# SoC.net
KiCad netlist of a schematic drawn in Altium Designer
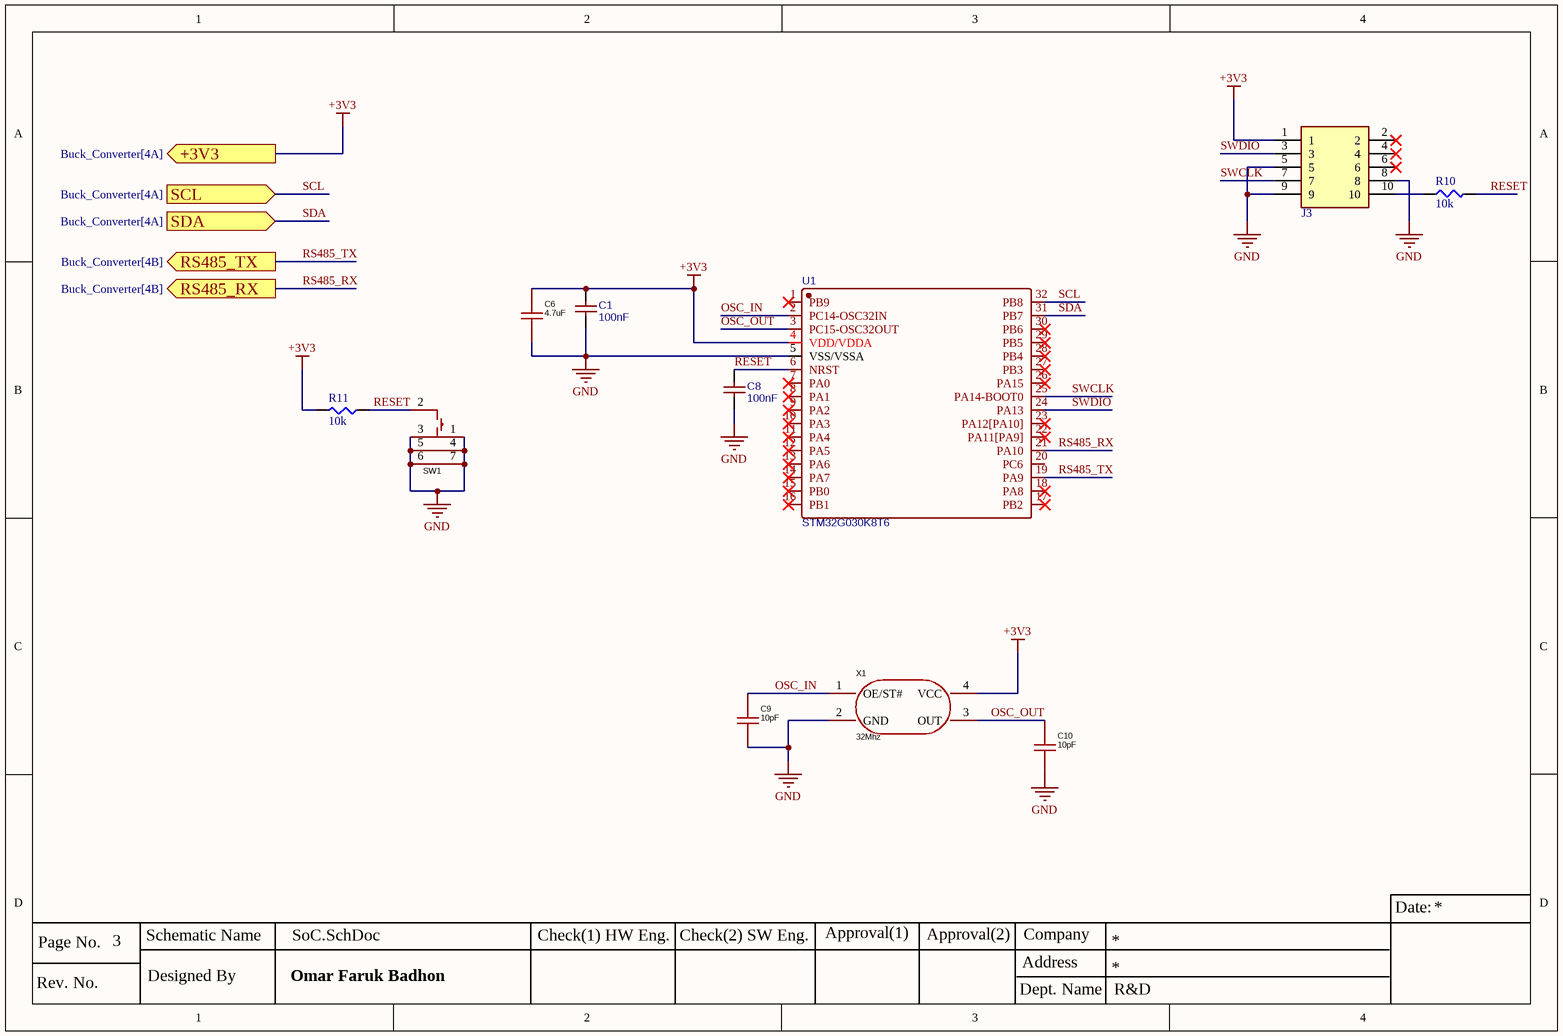
[diagram p0: SoC.SchDoc]

(export (version "E")
  (design (tool "Eeschema 10.0.6"))
  (components
    (comp (ref "C1")
      (value "100nF")
      (footprint "Cap 100nF 16V")
      (description "16V 100nF X7R ±10% 0603 Multilayer Ceramic Capacitors MLCC - SMD/SMT ROHS")
      (fields
        (field (name "MANUFACTURER") "muRata(村田)")
        (field (name "MANUFACTURER PART") "GRM188R71C104KA01D")
      )
      (libsource (lib "Sch lib") (part "Cap 100nF"))
    )
    (comp (ref "C6")
      (value "4.7uF")
      (footprint "Cap 4.7uF")
      (description "16V 4.7uF X7S ±10% 0603 Multilayer Ceramic Capacitors MLCC - SMD/SMT ROHS")
      (fields
        (field (name "MANUFACTURER") "muRata(村田)")
        (field (name "MANUFACTURER PART") "GRM188C71C475KE21D")
      )
      (libsource (lib "Sch lib") (part "GRM188C71C475KE21D"))
    )
    (comp (ref "C8")
      (value "100nF")
      (footprint "Cap 100nF 16V")
      (description "16V 100nF X7R ±10% 0603 Multilayer Ceramic Capacitors MLCC - SMD/SMT ROHS")
      (fields
        (field (name "MANUFACTURER") "muRata(村田)")
        (field (name "MANUFACTURER PART") "GRM188R71C104KA01D")
      )
      (libsource (lib "Sch lib") (part "Cap 100nF"))
    )
    (comp (ref "C9")
      (value "10pF")
      (footprint "Cap 10pF")
      (description "25V 10pF NP0 ±5% 0603  Multilayer Ceramic Capacitors MLCC - SMD/SMT ROHS")
      (fields
        (field (name "MANUFACTURER") "YAGEO(国巨)")
        (field (name "MANUFACTURER PART") "CC0603JRNPO8BN100")
      )
      (libsource (lib "Sch lib") (part "Cap 10pF"))
    )
    (comp (ref "C10")
      (value "10pF")
      (footprint "Cap 10pF")
      (description "25V 10pF NP0 ±5% 0603  Multilayer Ceramic Capacitors MLCC - SMD/SMT ROHS")
      (fields
        (field (name "MANUFACTURER") "YAGEO(国巨)")
        (field (name "MANUFACTURER PART") "CC0603JRNPO8BN100")
      )
      (libsource (lib "Sch lib") (part "Cap 10pF"))
    )
    (comp (ref "J3")
      (value "20021121-00010C4LF")
      (footprint "JTAG")
      (description "Headers & Wire Housings 1.27x1.27mm BTB, Hdr Unshrd, SMT, 10 Pos")
      (fields (field (name "MOUSER PART NUMBER") "649-202112100010C4LF"))
      (libsource (lib "Sch lib") (part "JTAG"))
    )
    (comp (ref "R10")
      (value "10k")
      (footprint "Res 10K")
      (description "RES SMD 10K OHM 1% 1/4W 0603")
      (fields
        (field (name "PART NUMBER") "ERJ-PA3F1002V")
        (field (name "DIGI-KEY PART NUMBER") "P10KBYCT-ND")
      )
      (libsource (lib "Sch lib") (part "ERJ-PA3F1002V_1"))
    )
    (comp (ref "R11")
      (value "10k")
      (footprint "Res 10K")
      (description "RES SMD 10K OHM 1% 1/4W 0603")
      (fields
        (field (name "PART NUMBER") "ERJ-PA3F1002V")
        (field (name "DIGI-KEY PART NUMBER") "P10KBYCT-ND")
      )
      (libsource (lib "Sch lib") (part "ERJ-PA3F1002V_1"))
    )
    (comp (ref "SW1")
      (value "TSA020B3418A02")
      (footprint "Push Button")
      (fields (field (name "MANUFACTURER") "BZCN(博众电气)"))
      (libsource (lib "Sch lib") (part "Push Button"))
    )
    (comp (ref "U1")
      (value "STM32G030K8T6")
      (footprint "STM32G030K8T6")
      (fields (field (name "MANUFACTURER") "ST(意法半导体)") (field (name "CONTRIBUTOR") "LCSC"))
      (libsource (lib "Sch lib") (part "STM32G030K8T6"))
    )
    (comp (ref "X1")
      (value "32Mhz")
      (footprint "Crystal 32MHz")
      (fields (field (name "MANUFACTURER") "EPSON(爱普生)") (field (name "MANUFACTURER PART") "X1G0044810009"))
      (libsource (lib "Sch lib") (part "Crystal"))
    )
  )
  (nets
    (net (code "1") (name "+3V3") (class "Default")
      (node (ref "C1") (pin "2") (pinfunction "2_2") (pintype "passive"))
      (node (ref "C6") (pin "1") (pinfunction "1_1") (pintype "passive"))
      (node (ref "J3") (pin "1") (pinfunction "1_1") (pintype "passive"))
      (node (ref "R11") (pin "2") (pinfunction "2_2") (pintype "passive"))
      (node (ref "U1") (pin "4") (pinfunction "VDD/VDDA_4") (pintype "passive"))
      (node (ref "X1") (pin "4") (pinfunction "VCC_4") (pintype "passive"))
    )
    (net (code "2") (name "/OSC_IN") (class "Default")
      (node (ref "C9") (pin "2") (pinfunction "2_2") (pintype "passive"))
      (node (ref "U1") (pin "2") (pinfunction "PC14-OSC32IN_2") (pintype "passive"))
      (node (ref "X1") (pin "1") (pinfunction "OE/ST#_1") (pintype "passive"))
    )
    (net (code "3") (name "/OSC_OUT") (class "Default")
      (node (ref "C10") (pin "2") (pinfunction "2_2") (pintype "passive"))
      (node (ref "U1") (pin "3") (pinfunction "PC15-OSC32OUT_3") (pintype "passive"))
      (node (ref "X1") (pin "3") (pinfunction "OUT_3") (pintype "passive"))
    )
    (net (code "4") (name "/RESET") (class "Default")
      (node (ref "C8") (pin "2") (pinfunction "2_2") (pintype "passive"))
      (node (ref "R10") (pin "2") (pinfunction "2_2") (pintype "passive"))
      (node (ref "R11") (pin "1") (pinfunction "1_1") (pintype "passive"))
      (node (ref "SW1") (pin "2") (pinfunction "2_2") (pintype "passive"))
      (node (ref "U1") (pin "6") (pinfunction "NRST_6") (pintype "passive"))
    )
    (net (code "5") (name "/RS485_RX") (class "Default")
      (node (ref "U1") (pin "21") (pinfunction "PA10_21") (pintype "passive"))
    )
    (net (code "6") (name "/RS485_TX") (class "Default")
      (node (ref "U1") (pin "19") (pinfunction "PA9_19") (pintype "passive"))
    )
    (net (code "7") (name "/SCL") (class "Default")
      (node (ref "U1") (pin "32") (pinfunction "PB8_32") (pintype "passive"))
    )
    (net (code "8") (name "/SDA") (class "Default")
      (node (ref "U1") (pin "31") (pinfunction "PB7_31") (pintype "passive"))
    )
    (net (code "9") (name "/SWCLK") (class "Default")
      (node (ref "J3") (pin "7") (pinfunction "7_7") (pintype "passive"))
      (node (ref "U1") (pin "25") (pinfunction "PA14-BOOT0_25") (pintype "passive"))
    )
    (net (code "10") (name "/SWDIO") (class "Default")
      (node (ref "J3") (pin "3") (pinfunction "3_3") (pintype "passive"))
      (node (ref "U1") (pin "24") (pinfunction "PA13_24") (pintype "passive"))
    )
    (net (code "11") (name "GND") (class "Default")
      (node (ref "C1") (pin "1") (pinfunction "1_1") (pintype "passive"))
      (node (ref "C10") (pin "1") (pinfunction "1_1") (pintype "passive"))
      (node (ref "C6") (pin "2") (pinfunction "2_2") (pintype "passive"))
      (node (ref "C8") (pin "1") (pinfunction "1_1") (pintype "passive"))
      (node (ref "C9") (pin "1") (pinfunction "1_1") (pintype "passive"))
      (node (ref "J3") (pin "5") (pinfunction "5_5") (pintype "passive"))
      (node (ref "J3") (pin "8") (pinfunction "8_8") (pintype "passive"))
      (node (ref "J3") (pin "9") (pinfunction "9_9") (pintype "passive"))
      (node (ref "SW1") (pin "1") (pinfunction "1_1") (pintype "passive"))
      (node (ref "SW1") (pin "3") (pinfunction "3_3") (pintype "passive"))
      (node (ref "SW1") (pin "4") (pinfunction "4_4") (pintype "passive"))
      (node (ref "SW1") (pin "5") (pinfunction "5_5") (pintype "passive"))
      (node (ref "SW1") (pin "6") (pinfunction "6_6") (pintype "passive"))
      (node (ref "SW1") (pin "7") (pinfunction "7_7") (pintype "passive"))
      (node (ref "U1") (pin "5") (pinfunction "VSS/VSSA_5") (pintype "passive"))
      (node (ref "X1") (pin "2") (pinfunction "GND_2") (pintype "passive"))
    )
    (net (code "12") (name "Net-(J3-Pad10)") (class "Default")
      (node (ref "J3") (pin "10") (pinfunction "10_10") (pintype "passive"))
      (node (ref "R10") (pin "1") (pinfunction "1_1") (pintype "passive"))
    )
    (net (code "13") (name "unconnected-(J3-Pad2)") (class "Default")
      (node (ref "J3") (pin "2") (pinfunction "2_2") (pintype "passive+no_connect"))
    )
    (net (code "14") (name "unconnected-(J3-Pad4)") (class "Default")
      (node (ref "J3") (pin "4") (pinfunction "4_4") (pintype "passive+no_connect"))
    )
    (net (code "15") (name "unconnected-(J3-Pad6)") (class "Default")
      (node (ref "J3") (pin "6") (pinfunction "6_6") (pintype "passive+no_connect"))
    )
    (net (code "16") (name "unconnected-(U1-PA0-Pad7)") (class "Default")
      (node (ref "U1") (pin "7") (pinfunction "PA0_7") (pintype "passive+no_connect"))
    )
    (net (code "17") (name "unconnected-(U1-PA1-Pad8)") (class "Default")
      (node (ref "U1") (pin "8") (pinfunction "PA1_8") (pintype "passive+no_connect"))
    )
    (net (code "18") (name "unconnected-(U1-PA2-Pad9)") (class "Default")
      (node (ref "U1") (pin "9") (pinfunction "PA2_9") (pintype "passive+no_connect"))
    )
    (net (code "19") (name "unconnected-(U1-PA3-Pad10)") (class "Default")
      (node (ref "U1") (pin "10") (pinfunction "PA3_10") (pintype "passive+no_connect"))
    )
    (net (code "20") (name "unconnected-(U1-PA4-Pad11)") (class "Default")
      (node (ref "U1") (pin "11") (pinfunction "PA4_11") (pintype "passive+no_connect"))
    )
    (net (code "21") (name "unconnected-(U1-PA5-Pad12)") (class "Default")
      (node (ref "U1") (pin "12") (pinfunction "PA5_12") (pintype "passive+no_connect"))
    )
    (net (code "22") (name "unconnected-(U1-PA6-Pad13)") (class "Default")
      (node (ref "U1") (pin "13") (pinfunction "PA6_13") (pintype "passive+no_connect"))
    )
    (net (code "23") (name "unconnected-(U1-PA7-Pad14)") (class "Default")
      (node (ref "U1") (pin "14") (pinfunction "PA7_14") (pintype "passive+no_connect"))
    )
    (net (code "24") (name "unconnected-(U1-PA8-Pad18)") (class "Default")
      (node (ref "U1") (pin "18") (pinfunction "PA8_18") (pintype "passive+no_connect"))
    )
    (net (code "25") (name "unconnected-(U1-PA11[PA9]-Pad22)") (class "Default")
      (node (ref "U1") (pin "22") (pinfunction "PA11[PA9]_22") (pintype "passive+no_connect"))
    )
    (net (code "26") (name "unconnected-(U1-PA12[PA10]-Pad23)") (class "Default")
      (node (ref "U1") (pin "23") (pinfunction "PA12[PA10]_23") (pintype "passive+no_connect"))
    )
    (net (code "27") (name "unconnected-(U1-PA15-Pad26)") (class "Default")
      (node (ref "U1") (pin "26") (pinfunction "PA15_26") (pintype "passive+no_connect"))
    )
    (net (code "28") (name "unconnected-(U1-PB0-Pad15)") (class "Default")
      (node (ref "U1") (pin "15") (pinfunction "PB0_15") (pintype "passive+no_connect"))
    )
    (net (code "29") (name "unconnected-(U1-PB1-Pad16)") (class "Default")
      (node (ref "U1") (pin "16") (pinfunction "PB1_16") (pintype "passive+no_connect"))
    )
    (net (code "30") (name "unconnected-(U1-PB2-Pad17)") (class "Default")
      (node (ref "U1") (pin "17") (pinfunction "PB2_17") (pintype "passive+no_connect"))
    )
    (net (code "31") (name "unconnected-(U1-PB3-Pad27)") (class "Default")
      (node (ref "U1") (pin "27") (pinfunction "PB3_27") (pintype "passive+no_connect"))
    )
    (net (code "32") (name "unconnected-(U1-PB4-Pad28)") (class "Default")
      (node (ref "U1") (pin "28") (pinfunction "PB4_28") (pintype "passive+no_connect"))
    )
    (net (code "33") (name "unconnected-(U1-PB5-Pad29)") (class "Default")
      (node (ref "U1") (pin "29") (pinfunction "PB5_29") (pintype "passive+no_connect"))
    )
    (net (code "34") (name "unconnected-(U1-PB6-Pad30)") (class "Default")
      (node (ref "U1") (pin "30") (pinfunction "PB6_30") (pintype "passive+no_connect"))
    )
    (net (code "35") (name "unconnected-(U1-PB9-Pad1)") (class "Default")
      (node (ref "U1") (pin "1") (pinfunction "PB9_1") (pintype "passive+no_connect"))
    )
    (net (code "36") (name "unconnected-(U1-PC6-Pad20)") (class "Default")
      (node (ref "U1") (pin "20") (pinfunction "PC6_20") (pintype "passive"))
    )
  )
)
